# 2_waffling60-SE_matrix.net
KiCad netlist of a schematic drawn in Altium Designer
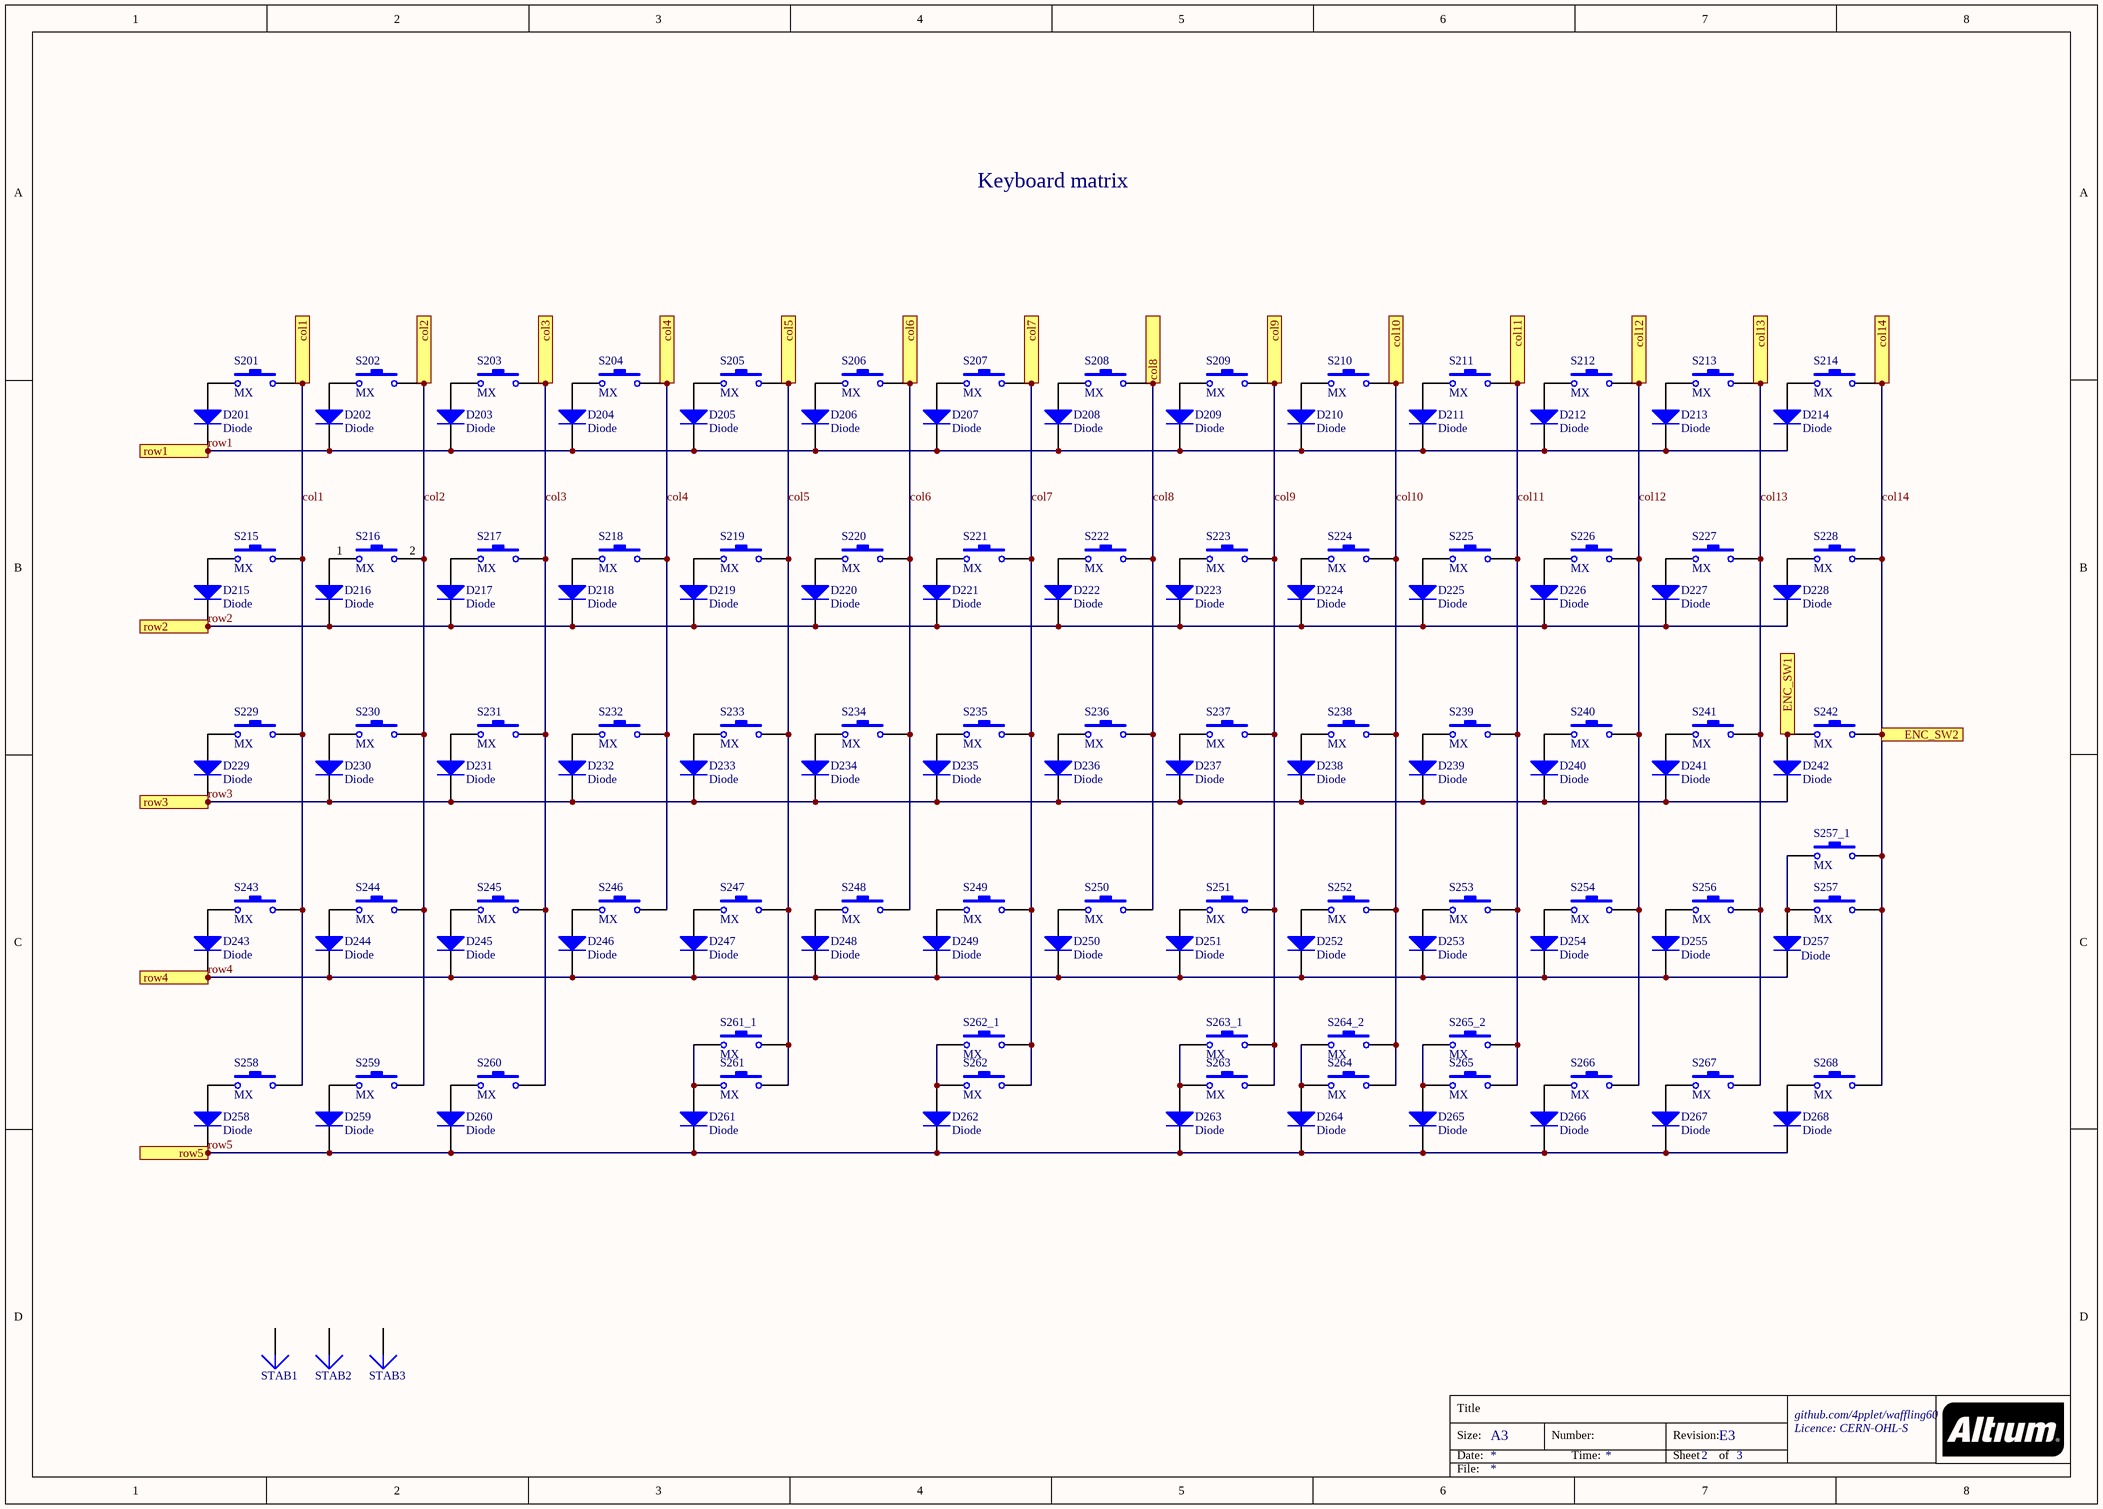
[diagram p0: 2_waffling60-SE_matrix.SchDoc]

(export (version "E")
  (design (tool "Eeschema 10.0.6"))
  (components
    (comp (ref "D201")
      (value "Diode")
      (footprint "SOD-123")
      (description "Default Diode")
      (fields (field (name "LCSC PART #") "C81598") (field (name "MRF.PART") "1N4148W"))
      (libsource (lib "Miscellaneous Devices") (part "Diode"))
    )
    (comp (ref "D202")
      (value "Diode")
      (footprint "SOD-123")
      (description "Default Diode")
      (fields (field (name "LCSC PART #") "C81598") (field (name "MRF.PART") "1N4148W"))
      (libsource (lib "Miscellaneous Devices") (part "Diode"))
    )
    (comp (ref "D203")
      (value "Diode")
      (footprint "SOD-123")
      (description "Default Diode")
      (fields (field (name "LCSC PART #") "C81598") (field (name "MRF.PART") "1N4148W"))
      (libsource (lib "Miscellaneous Devices") (part "Diode"))
    )
    (comp (ref "D204")
      (value "Diode")
      (footprint "SOD-123")
      (description "Default Diode")
      (fields (field (name "LCSC PART #") "C81598") (field (name "MRF.PART") "1N4148W"))
      (libsource (lib "Miscellaneous Devices") (part "Diode"))
    )
    (comp (ref "D205")
      (value "Diode")
      (footprint "SOD-123")
      (description "Default Diode")
      (fields (field (name "LCSC PART #") "C81598") (field (name "MRF.PART") "1N4148W"))
      (libsource (lib "Miscellaneous Devices") (part "Diode"))
    )
    (comp (ref "D206")
      (value "Diode")
      (footprint "SOD-123")
      (description "Default Diode")
      (fields (field (name "LCSC PART #") "C81598") (field (name "MRF.PART") "1N4148W"))
      (libsource (lib "Miscellaneous Devices") (part "Diode"))
    )
    (comp (ref "D207")
      (value "Diode")
      (footprint "SOD-123")
      (description "Default Diode")
      (fields (field (name "LCSC PART #") "C81598") (field (name "MRF.PART") "1N4148W"))
      (libsource (lib "Miscellaneous Devices") (part "Diode"))
    )
    (comp (ref "D208")
      (value "Diode")
      (footprint "SOD-123")
      (description "Default Diode")
      (fields (field (name "LCSC PART #") "C81598") (field (name "MRF.PART") "1N4148W"))
      (libsource (lib "Miscellaneous Devices") (part "Diode"))
    )
    (comp (ref "D209")
      (value "Diode")
      (footprint "SOD-123")
      (description "Default Diode")
      (fields (field (name "LCSC PART #") "C81598") (field (name "MRF.PART") "1N4148W"))
      (libsource (lib "Miscellaneous Devices") (part "Diode"))
    )
    (comp (ref "D210")
      (value "Diode")
      (footprint "SOD-123")
      (description "Default Diode")
      (fields (field (name "LCSC PART #") "C81598") (field (name "MRF.PART") "1N4148W"))
      (libsource (lib "Miscellaneous Devices") (part "Diode"))
    )
    (comp (ref "D211")
      (value "Diode")
      (footprint "SOD-123")
      (description "Default Diode")
      (fields (field (name "LCSC PART #") "C81598") (field (name "MRF.PART") "1N4148W"))
      (libsource (lib "Miscellaneous Devices") (part "Diode"))
    )
    (comp (ref "D212")
      (value "Diode")
      (footprint "SOD-123")
      (description "Default Diode")
      (fields (field (name "LCSC PART #") "C81598") (field (name "MRF.PART") "1N4148W"))
      (libsource (lib "Miscellaneous Devices") (part "Diode"))
    )
    (comp (ref "D213")
      (value "Diode")
      (footprint "SOD-123")
      (description "Default Diode")
      (fields (field (name "LCSC PART #") "C81598") (field (name "MRF.PART") "1N4148W"))
      (libsource (lib "Miscellaneous Devices") (part "Diode"))
    )
    (comp (ref "D214")
      (value "Diode")
      (footprint "SOD-123")
      (description "Default Diode")
      (fields (field (name "LCSC PART #") "C81598") (field (name "MRF.PART") "1N4148W"))
      (libsource (lib "Miscellaneous Devices") (part "Diode"))
    )
    (comp (ref "D215")
      (value "Diode")
      (footprint "SOD-123")
      (description "Default Diode")
      (fields (field (name "LCSC PART #") "C81598") (field (name "MRF.PART") "1N4148W"))
      (libsource (lib "Miscellaneous Devices") (part "Diode"))
    )
    (comp (ref "D216")
      (value "Diode")
      (footprint "SOD-123")
      (description "Default Diode")
      (fields (field (name "LCSC PART #") "C81598") (field (name "MRF.PART") "1N4148W"))
      (libsource (lib "Miscellaneous Devices") (part "Diode"))
    )
    (comp (ref "D217")
      (value "Diode")
      (footprint "SOD-123")
      (description "Default Diode")
      (fields (field (name "LCSC PART #") "C81598") (field (name "MRF.PART") "1N4148W"))
      (libsource (lib "Miscellaneous Devices") (part "Diode"))
    )
    (comp (ref "D218")
      (value "Diode")
      (footprint "SOD-123")
      (description "Default Diode")
      (fields (field (name "LCSC PART #") "C81598") (field (name "MRF.PART") "1N4148W"))
      (libsource (lib "Miscellaneous Devices") (part "Diode"))
    )
    (comp (ref "D219")
      (value "Diode")
      (footprint "SOD-123")
      (description "Default Diode")
      (fields (field (name "LCSC PART #") "C81598") (field (name "MRF.PART") "1N4148W"))
      (libsource (lib "Miscellaneous Devices") (part "Diode"))
    )
    (comp (ref "D220")
      (value "Diode")
      (footprint "SOD-123")
      (description "Default Diode")
      (fields (field (name "LCSC PART #") "C81598") (field (name "MRF.PART") "1N4148W"))
      (libsource (lib "Miscellaneous Devices") (part "Diode"))
    )
    (comp (ref "D221")
      (value "Diode")
      (footprint "SOD-123")
      (description "Default Diode")
      (fields (field (name "LCSC PART #") "C81598") (field (name "MRF.PART") "1N4148W"))
      (libsource (lib "Miscellaneous Devices") (part "Diode"))
    )
    (comp (ref "D222")
      (value "Diode")
      (footprint "SOD-123")
      (description "Default Diode")
      (fields (field (name "LCSC PART #") "C81598") (field (name "MRF.PART") "1N4148W"))
      (libsource (lib "Miscellaneous Devices") (part "Diode"))
    )
    (comp (ref "D223")
      (value "Diode")
      (footprint "SOD-123")
      (description "Default Diode")
      (fields (field (name "LCSC PART #") "C81598") (field (name "MRF.PART") "1N4148W"))
      (libsource (lib "Miscellaneous Devices") (part "Diode"))
    )
    (comp (ref "D224")
      (value "Diode")
      (footprint "SOD-123")
      (description "Default Diode")
      (fields (field (name "LCSC PART #") "C81598") (field (name "MRF.PART") "1N4148W"))
      (libsource (lib "Miscellaneous Devices") (part "Diode"))
    )
    (comp (ref "D225")
      (value "Diode")
      (footprint "SOD-123")
      (description "Default Diode")
      (fields (field (name "LCSC PART #") "C81598") (field (name "MRF.PART") "1N4148W"))
      (libsource (lib "Miscellaneous Devices") (part "Diode"))
    )
    (comp (ref "D226")
      (value "Diode")
      (footprint "SOD-123")
      (description "Default Diode")
      (fields (field (name "LCSC PART #") "C81598") (field (name "MRF.PART") "1N4148W"))
      (libsource (lib "Miscellaneous Devices") (part "Diode"))
    )
    (comp (ref "D227")
      (value "Diode")
      (footprint "SOD-123")
      (description "Default Diode")
      (fields (field (name "LCSC PART #") "C81598") (field (name "MRF.PART") "1N4148W"))
      (libsource (lib "Miscellaneous Devices") (part "Diode"))
    )
    (comp (ref "D228")
      (value "Diode")
      (footprint "SOD-123")
      (description "Default Diode")
      (fields (field (name "LCSC PART #") "C81598") (field (name "MRF.PART") "1N4148W"))
      (libsource (lib "Miscellaneous Devices") (part "Diode"))
    )
    (comp (ref "D229")
      (value "Diode")
      (footprint "SOD-123")
      (description "Default Diode")
      (fields (field (name "LCSC PART #") "C81598") (field (name "MRF.PART") "1N4148W"))
      (libsource (lib "Miscellaneous Devices") (part "Diode"))
    )
    (comp (ref "D230")
      (value "Diode")
      (footprint "SOD-123")
      (description "Default Diode")
      (fields (field (name "LCSC PART #") "C81598") (field (name "MRF.PART") "1N4148W"))
      (libsource (lib "Miscellaneous Devices") (part "Diode"))
    )
    (comp (ref "D231")
      (value "Diode")
      (footprint "SOD-123")
      (description "Default Diode")
      (fields (field (name "LCSC PART #") "C81598") (field (name "MRF.PART") "1N4148W"))
      (libsource (lib "Miscellaneous Devices") (part "Diode"))
    )
    (comp (ref "D232")
      (value "Diode")
      (footprint "SOD-123")
      (description "Default Diode")
      (fields (field (name "LCSC PART #") "C81598") (field (name "MRF.PART") "1N4148W"))
      (libsource (lib "Miscellaneous Devices") (part "Diode"))
    )
    (comp (ref "D233")
      (value "Diode")
      (footprint "SOD-123")
      (description "Default Diode")
      (fields (field (name "LCSC PART #") "C81598") (field (name "MRF.PART") "1N4148W"))
      (libsource (lib "Miscellaneous Devices") (part "Diode"))
    )
    (comp (ref "D234")
      (value "Diode")
      (footprint "SOD-123")
      (description "Default Diode")
      (fields (field (name "LCSC PART #") "C81598") (field (name "MRF.PART") "1N4148W"))
      (libsource (lib "Miscellaneous Devices") (part "Diode"))
    )
    (comp (ref "D235")
      (value "Diode")
      (footprint "SOD-123")
      (description "Default Diode")
      (fields (field (name "LCSC PART #") "C81598") (field (name "MRF.PART") "1N4148W"))
      (libsource (lib "Miscellaneous Devices") (part "Diode"))
    )
    (comp (ref "D236")
      (value "Diode")
      (footprint "SOD-123")
      (description "Default Diode")
      (fields (field (name "LCSC PART #") "C81598") (field (name "MRF.PART") "1N4148W"))
      (libsource (lib "Miscellaneous Devices") (part "Diode"))
    )
    (comp (ref "D237")
      (value "Diode")
      (footprint "SOD-123")
      (description "Default Diode")
      (fields (field (name "LCSC PART #") "C81598") (field (name "MRF.PART") "1N4148W"))
      (libsource (lib "Miscellaneous Devices") (part "Diode"))
    )
    (comp (ref "D238")
      (value "Diode")
      (footprint "SOD-123")
      (description "Default Diode")
      (fields (field (name "LCSC PART #") "C81598") (field (name "MRF.PART") "1N4148W"))
      (libsource (lib "Miscellaneous Devices") (part "Diode"))
    )
    (comp (ref "D239")
      (value "Diode")
      (footprint "SOD-123")
      (description "Default Diode")
      (fields (field (name "LCSC PART #") "C81598") (field (name "MRF.PART") "1N4148W"))
      (libsource (lib "Miscellaneous Devices") (part "Diode"))
    )
    (comp (ref "D240")
      (value "Diode")
      (footprint "SOD-123")
      (description "Default Diode")
      (fields (field (name "LCSC PART #") "C81598") (field (name "MRF.PART") "1N4148W"))
      (libsource (lib "Miscellaneous Devices") (part "Diode"))
    )
    (comp (ref "D241")
      (value "Diode")
      (footprint "SOD-123")
      (description "Default Diode")
      (fields (field (name "LCSC PART #") "C81598") (field (name "MRF.PART") "1N4148W"))
      (libsource (lib "Miscellaneous Devices") (part "Diode"))
    )
    (comp (ref "D242")
      (value "Diode")
      (footprint "SOD-123")
      (description "Default Diode")
      (fields (field (name "LCSC PART #") "C81598") (field (name "MRF.PART") "1N4148W"))
      (libsource (lib "Miscellaneous Devices") (part "Diode"))
    )
    (comp (ref "D243")
      (value "Diode")
      (footprint "SOD-123")
      (description "Default Diode")
      (fields (field (name "LCSC PART #") "C81598") (field (name "MRF.PART") "1N4148W"))
      (libsource (lib "Miscellaneous Devices") (part "Diode"))
    )
    (comp (ref "D244")
      (value "Diode")
      (footprint "SOD-123")
      (description "Default Diode")
      (fields (field (name "LCSC PART #") "C81598") (field (name "MRF.PART") "1N4148W"))
      (libsource (lib "Miscellaneous Devices") (part "Diode"))
    )
    (comp (ref "D245")
      (value "Diode")
      (footprint "SOD-123")
      (description "Default Diode")
      (fields (field (name "LCSC PART #") "C81598") (field (name "MRF.PART") "1N4148W"))
      (libsource (lib "Miscellaneous Devices") (part "Diode"))
    )
    (comp (ref "D246")
      (value "Diode")
      (footprint "SOD-123")
      (description "Default Diode")
      (fields (field (name "LCSC PART #") "C81598") (field (name "MRF.PART") "1N4148W"))
      (libsource (lib "Miscellaneous Devices") (part "Diode"))
    )
    (comp (ref "D247")
      (value "Diode")
      (footprint "SOD-123")
      (description "Default Diode")
      (fields (field (name "LCSC PART #") "C81598") (field (name "MRF.PART") "1N4148W"))
      (libsource (lib "Miscellaneous Devices") (part "Diode"))
    )
    (comp (ref "D248")
      (value "Diode")
      (footprint "SOD-123")
      (description "Default Diode")
      (fields (field (name "LCSC PART #") "C81598") (field (name "MRF.PART") "1N4148W"))
      (libsource (lib "Miscellaneous Devices") (part "Diode"))
    )
    (comp (ref "D249")
      (value "Diode")
      (footprint "SOD-123")
      (description "Default Diode")
      (fields (field (name "LCSC PART #") "C81598") (field (name "MRF.PART") "1N4148W"))
      (libsource (lib "Miscellaneous Devices") (part "Diode"))
    )
    (comp (ref "D250")
      (value "Diode")
      (footprint "SOD-123")
      (description "Default Diode")
      (fields (field (name "LCSC PART #") "C81598") (field (name "MRF.PART") "1N4148W"))
      (libsource (lib "Miscellaneous Devices") (part "Diode"))
    )
    (comp (ref "D251")
      (value "Diode")
      (footprint "SOD-123")
      (description "Default Diode")
      (fields (field (name "LCSC PART #") "C81598") (field (name "MRF.PART") "1N4148W"))
      (libsource (lib "Miscellaneous Devices") (part "Diode"))
    )
    (comp (ref "D252")
      (value "Diode")
      (footprint "SOD-123")
      (description "Default Diode")
      (fields (field (name "LCSC PART #") "C81598") (field (name "MRF.PART") "1N4148W"))
      (libsource (lib "Miscellaneous Devices") (part "Diode"))
    )
    (comp (ref "D253")
      (value "Diode")
      (footprint "SOD-123")
      (description "Default Diode")
      (fields (field (name "LCSC PART #") "C81598") (field (name "MRF.PART") "1N4148W"))
      (libsource (lib "Miscellaneous Devices") (part "Diode"))
    )
    (comp (ref "D254")
      (value "Diode")
      (footprint "SOD-123")
      (description "Default Diode")
      (fields (field (name "LCSC PART #") "C81598") (field (name "MRF.PART") "1N4148W"))
      (libsource (lib "Miscellaneous Devices") (part "Diode"))
    )
    (comp (ref "D255")
      (value "Diode")
      (footprint "SOD-123")
      (description "Default Diode")
      (fields (field (name "LCSC PART #") "C81598") (field (name "MRF.PART") "1N4148W"))
      (libsource (lib "Miscellaneous Devices") (part "Diode"))
    )
    (comp (ref "D257")
      (value "Diode")
      (footprint "SOD-123")
      (description "Default Diode")
      (fields (field (name "LCSC PART #") "C81598") (field (name "MRF.PART") "1N4148W"))
      (libsource (lib "Miscellaneous Devices") (part "Diode"))
    )
    (comp (ref "D258")
      (value "Diode")
      (footprint "SOD-123")
      (description "Default Diode")
      (fields (field (name "LCSC PART #") "C81598") (field (name "MRF.PART") "1N4148W"))
      (libsource (lib "Miscellaneous Devices") (part "Diode"))
    )
    (comp (ref "D259")
      (value "Diode")
      (footprint "SOD-123")
      (description "Default Diode")
      (fields (field (name "LCSC PART #") "C81598") (field (name "MRF.PART") "1N4148W"))
      (libsource (lib "Miscellaneous Devices") (part "Diode"))
    )
    (comp (ref "D260")
      (value "Diode")
      (footprint "SOD-123")
      (description "Default Diode")
      (fields (field (name "LCSC PART #") "C81598") (field (name "MRF.PART") "1N4148W"))
      (libsource (lib "Miscellaneous Devices") (part "Diode"))
    )
    (comp (ref "D261")
      (value "Diode")
      (footprint "SOD-123")
      (description "Default Diode")
      (fields (field (name "LCSC PART #") "C81598") (field (name "MRF.PART") "1N4148W"))
      (libsource (lib "Miscellaneous Devices") (part "Diode"))
    )
    (comp (ref "D262")
      (value "Diode")
      (footprint "SOD-123")
      (description "Default Diode")
      (fields (field (name "LCSC PART #") "C81598") (field (name "MRF.PART") "1N4148W"))
      (libsource (lib "Miscellaneous Devices") (part "Diode"))
    )
    (comp (ref "D263")
      (value "Diode")
      (footprint "SOD-123")
      (description "Default Diode")
      (fields (field (name "LCSC PART #") "C81598") (field (name "MRF.PART") "1N4148W"))
      (libsource (lib "Miscellaneous Devices") (part "Diode"))
    )
    (comp (ref "D264")
      (value "Diode")
      (footprint "SOD-123")
      (description "Default Diode")
      (fields (field (name "LCSC PART #") "C81598") (field (name "MRF.PART") "1N4148W"))
      (libsource (lib "Miscellaneous Devices") (part "Diode"))
    )
    (comp (ref "D265")
      (value "Diode")
      (footprint "SOD-123")
      (description "Default Diode")
      (fields (field (name "LCSC PART #") "C81598") (field (name "MRF.PART") "1N4148W"))
      (libsource (lib "Miscellaneous Devices") (part "Diode"))
    )
    (comp (ref "D266")
      (value "Diode")
      (footprint "SOD-123")
      (description "Default Diode")
      (fields (field (name "LCSC PART #") "C81598") (field (name "MRF.PART") "1N4148W"))
      (libsource (lib "Miscellaneous Devices") (part "Diode"))
    )
    (comp (ref "D267")
      (value "Diode")
      (footprint "SOD-123")
      (description "Default Diode")
      (fields (field (name "LCSC PART #") "C81598") (field (name "MRF.PART") "1N4148W"))
      (libsource (lib "Miscellaneous Devices") (part "Diode"))
    )
    (comp (ref "D268")
      (value "Diode")
      (footprint "SOD-123")
      (description "Default Diode")
      (fields (field (name "LCSC PART #") "C81598") (field (name "MRF.PART") "1N4148W"))
      (libsource (lib "Miscellaneous Devices") (part "Diode"))
    )
    (comp (ref "S201")
      (value "MX")
      (footprint "MX-switch - switched pol")
      (description "Switch")
      (libsource (lib "Miscellaneous Devices") (part "SW-PB"))
    )
    (comp (ref "S202")
      (value "MX")
      (footprint "MX-switch")
      (description "Switch")
      (libsource (lib "Miscellaneous Devices") (part "SW-PB"))
    )
    (comp (ref "S203")
      (value "MX")
      (footprint "MX-switch - switched pol")
      (description "Switch")
      (libsource (lib "Miscellaneous Devices") (part "SW-PB"))
    )
    (comp (ref "S204")
      (value "MX")
      (footprint "MX-switch - switched pol")
      (description "Switch")
      (libsource (lib "Miscellaneous Devices") (part "SW-PB"))
    )
    (comp (ref "S205")
      (value "MX")
      (footprint "MX-switch - switched pol")
      (description "Switch")
      (libsource (lib "Miscellaneous Devices") (part "SW-PB"))
    )
    (comp (ref "S206")
      (value "MX")
      (footprint "MX-switch - switched pol")
      (description "Switch")
      (libsource (lib "Miscellaneous Devices") (part "SW-PB"))
    )
    (comp (ref "S207")
      (value "MX")
      (footprint "MX-switch - switched pol")
      (description "Switch")
      (libsource (lib "Miscellaneous Devices") (part "SW-PB"))
    )
    (comp (ref "S208")
      (value "MX")
      (footprint "MX-switch - switched pol")
      (description "Switch")
      (libsource (lib "Miscellaneous Devices") (part "SW-PB"))
    )
    (comp (ref "S209")
      (value "MX")
      (footprint "MX-switch - switched pol")
      (description "Switch")
      (libsource (lib "Miscellaneous Devices") (part "SW-PB"))
    )
    (comp (ref "S210")
      (value "MX")
      (footprint "MX-switch - switched pol")
      (description "Switch")
      (libsource (lib "Miscellaneous Devices") (part "SW-PB"))
    )
    (comp (ref "S211")
      (value "MX")
      (footprint "MX-switch - switched pol")
      (description "Switch")
      (libsource (lib "Miscellaneous Devices") (part "SW-PB"))
    )
    (comp (ref "S212")
      (value "MX")
      (footprint "MX-switch - switched pol")
      (description "Switch")
      (libsource (lib "Miscellaneous Devices") (part "SW-PB"))
    )
    (comp (ref "S213")
      (value "MX")
      (footprint "MX-switch - switched pol")
      (description "Switch")
      (libsource (lib "Miscellaneous Devices") (part "SW-PB"))
    )
    (comp (ref "S214")
      (value "MX")
      (footprint "MX-switch")
      (description "Switch")
      (libsource (lib "Miscellaneous Devices") (part "SW-PB"))
    )
    (comp (ref "S215")
      (value "MX")
      (footprint "MX-switch - switched pol")
      (description "TAB")
      (libsource (lib "Miscellaneous Devices") (part "SW-PB"))
    )
    (comp (ref "S216")
      (value "MX")
      (footprint "MX-switch")
      (description "Switch")
      (libsource (lib "") (part "SW-PB_1"))
    )
    (comp (ref "S217")
      (value "MX")
      (footprint "MX-switch - switched pol")
      (description "Switch")
      (libsource (lib "Miscellaneous Devices") (part "SW-PB"))
    )
    (comp (ref "S218")
      (value "MX")
      (footprint "MX-switch - switched pol")
      (description "Switch")
      (libsource (lib "Miscellaneous Devices") (part "SW-PB"))
    )
    (comp (ref "S219")
      (value "MX")
      (footprint "MX-switch - switched pol")
      (description "Switch")
      (libsource (lib "Miscellaneous Devices") (part "SW-PB"))
    )
    (comp (ref "S220")
      (value "MX")
      (footprint "MX-switch - switched pol")
      (description "Switch")
      (libsource (lib "Miscellaneous Devices") (part "SW-PB"))
    )
    (comp (ref "S221")
      (value "MX")
      (footprint "MX-switch - switched pol")
      (description "Switch")
      (libsource (lib "Miscellaneous Devices") (part "SW-PB"))
    )
    (comp (ref "S222")
      (value "MX")
      (footprint "MX-switch - switched pol")
      (description "Switch")
      (libsource (lib "Miscellaneous Devices") (part "SW-PB"))
    )
    (comp (ref "S223")
      (value "MX")
      (footprint "MX-switch - switched pol")
      (description "Switch")
      (libsource (lib "Miscellaneous Devices") (part "SW-PB"))
    )
    (comp (ref "S224")
      (value "MX")
      (footprint "MX-switch - switched pol")
      (description "Switch")
      (libsource (lib "Miscellaneous Devices") (part "SW-PB"))
    )
    (comp (ref "S225")
      (value "MX")
      (footprint "MX-switch - switched pol")
      (description "Switch")
      (libsource (lib "Miscellaneous Devices") (part "SW-PB"))
    )
    (comp (ref "S226")
      (value "MX")
      (footprint "MX-switch")
      (description "Switch")
      (libsource (lib "Miscellaneous Devices") (part "SW-PB"))
    )
    (comp (ref "S227")
      (value "MX")
      (footprint "MX-switch")
      (description "Switch")
      (libsource (lib "Miscellaneous Devices") (part "SW-PB"))
    )
    (comp (ref "S228")
      (value "MX")
      (footprint "MX-switch - 1.5U")
      (description "Switch")
      (libsource (lib "Miscellaneous Devices") (part "SW-PB"))
    )
    (comp (ref "S229")
      (value "MX")
      (footprint "MX-switch - CAPS")
      (description "Switch")
      (libsource (lib "Miscellaneous Devices") (part "SW-PB"))
    )
    (comp (ref "S230")
      (value "MX")
      (footprint "MX-switch")
      (description "Switch")
      (libsource (lib "Miscellaneous Devices") (part "SW-PB"))
    )
    (comp (ref "S231")
      (value "MX")
      (footprint "MX-switch - switched pol")
      (description "Switch")
      (libsource (lib "Miscellaneous Devices") (part "SW-PB"))
    )
    (comp (ref "S232")
      (value "MX")
      (footprint "MX-switch - switched pol")
      (description "Switch")
      (libsource (lib "Miscellaneous Devices") (part "SW-PB"))
    )
    (comp (ref "S233")
      (value "MX")
      (footprint "MX-switch - switched pol")
      (description "Switch")
      (libsource (lib "Miscellaneous Devices") (part "SW-PB"))
    )
    (comp (ref "S234")
      (value "MX")
      (footprint "MX-switch - switched pol")
      (description "Switch")
      (libsource (lib "Miscellaneous Devices") (part "SW-PB"))
    )
    (comp (ref "S235")
      (value "MX")
      (footprint "MX-switch - switched pol")
      (description "Switch")
      (libsource (lib "Miscellaneous Devices") (part "SW-PB"))
    )
    (comp (ref "S236")
      (value "MX")
      (footprint "MX-switch - switched pol")
      (description "Switch")
      (libsource (lib "Miscellaneous Devices") (part "SW-PB"))
    )
    (comp (ref "S237")
      (value "MX")
      (footprint "MX-switch - switched pol")
      (description "Switch")
      (libsource (lib "Miscellaneous Devices") (part "SW-PB"))
    )
    (comp (ref "S238")
      (value "MX")
      (footprint "MX-switch - switched pol")
      (description "Switch")
      (libsource (lib "Miscellaneous Devices") (part "SW-PB"))
    )
    (comp (ref "S239")
      (value "MX")
      (footprint "MX-switch - switched pol")
      (description "Switch")
      (libsource (lib "Miscellaneous Devices") (part "SW-PB"))
    )
    (comp (ref "S240")
      (value "MX")
      (footprint "MX-switch - switched pol")
      (description "Switch")
      (libsource (lib "Miscellaneous Devices") (part "SW-PB"))
    )
    (comp (ref "S241")
      (value "MX")
      (footprint "MX-switch")
      (description "Switch")
      (libsource (lib "Miscellaneous Devices") (part "SW-PB"))
    )
    (comp (ref "S242")
      (value "MX")
      (footprint "MX-switch - backspace")
      (description "Switch")
      (libsource (lib "Miscellaneous Devices") (part "SW-PB"))
    )
    (comp (ref "S243")
      (value "MX")
      (footprint "MX-switch - Left shift")
      (description "Switch")
      (libsource (lib "Miscellaneous Devices") (part "SW-PB"))
    )
    (comp (ref "S244")
      (value "MX")
      (footprint "MX-switch")
      (description "Switch")
      (libsource (lib "Miscellaneous Devices") (part "SW-PB"))
    )
    (comp (ref "S245")
      (value "MX")
      (footprint "MX-switch - switched pol")
      (description "Switch")
      (libsource (lib "Miscellaneous Devices") (part "SW-PB"))
    )
    (comp (ref "S246")
      (value "MX")
      (footprint "MX-switch - switched pol")
      (description "Switch")
      (libsource (lib "Miscellaneous Devices") (part "SW-PB"))
    )
    (comp (ref "S247")
      (value "MX")
      (footprint "MX-switch - switched pol")
      (description "Switch")
      (libsource (lib "Miscellaneous Devices") (part "SW-PB"))
    )
    (comp (ref "S248")
      (value "MX")
      (footprint "MX-switch - switched pol")
      (description "Switch")
      (libsource (lib "Miscellaneous Devices") (part "SW-PB"))
    )
    (comp (ref "S249")
      (value "MX")
      (footprint "MX-switch - switched pol")
      (description "Switch")
      (libsource (lib "Miscellaneous Devices") (part "SW-PB"))
    )
    (comp (ref "S250")
      (value "MX")
      (footprint "MX-switch - switched pol")
      (description "Switch")
      (libsource (lib "Miscellaneous Devices") (part "SW-PB"))
    )
    (comp (ref "S251")
      (value "MX")
      (footprint "MX-switch - switched pol")
      (description "Switch")
      (libsource (lib "Miscellaneous Devices") (part "SW-PB"))
    )
    (comp (ref "S252")
      (value "MX")
      (footprint "MX-switch - switched pol")
      (description "Switch")
      (libsource (lib "Miscellaneous Devices") (part "SW-PB"))
    )
    (comp (ref "S253")
      (value "MX")
      (footprint "MX-switch - switched pol")
      (description "Switch")
      (libsource (lib "Miscellaneous Devices") (part "SW-PB"))
    )
    (comp (ref "S254")
      (value "MX")
      (footprint "MX-switch - switched pol")
      (description "Switch")
      (libsource (lib "Miscellaneous Devices") (part "SW-PB"))
    )
    (comp (ref "S256")
      (value "MX")
      (footprint "MX-switch - right shift")
      (description "Switch")
      (libsource (lib "Miscellaneous Devices") (part "SW-PB"))
    )
    (comp (ref "S257")
      (value "MX")
      (footprint "MX-switch")
      (description "Switch")
      (libsource (lib "Miscellaneous Devices") (part "SW-PB"))
    )
    (comp (ref "S257_1")
      (value "MX")
      (footprint "MX-switch")
      (description "Switch")
      (libsource (lib "Miscellaneous Devices") (part "SW-PB"))
    )
    (comp (ref "S258")
      (value "MX")
      (footprint "MX-switch - 1.5u MOD-L")
      (description "Switch")
      (libsource (lib "Miscellaneous Devices") (part "SW-PB"))
    )
    (comp (ref "S259")
      (value "MX")
      (footprint "MX-switch - 1u MOD-L")
      (description "Switch")
      (libsource (lib "Miscellaneous Devices") (part "SW-PB"))
    )
    (comp (ref "S260")
      (value "MX")
      (footprint "MX-switch - 1.5u MOD-L")
      (description "Switch")
      (libsource (lib "Miscellaneous Devices") (part "SW-PB"))
    )
    (comp (ref "S261")
      (value "MX")
      (footprint "MX-SWITCH - L SPLIT SPACE_V2")
      (description "Switch")
      (libsource (lib "Miscellaneous Devices") (part "SW-PB"))
    )
    (comp (ref "S261_1")
      (value "MX")
      (footprint "MX-switch - 3U - rotated stab")
      (description "Switch")
      (libsource (lib "Miscellaneous Devices") (part "SW-PB"))
    )
    (comp (ref "S262")
      (value "MX")
      (footprint "MX-SWITCH - SPACE_7U+6.27U+6U")
      (description "Switch")
      (libsource (lib "Miscellaneous Devices") (part "SW-PB"))
    )
    (comp (ref "S262_1")
      (value "MX")
      (footprint "MX-switch - switched pol")
      (description "Switch")
      (libsource (lib "Miscellaneous Devices") (part "SW-PB"))
    )
    (comp (ref "S263")
      (value "MX")
      (footprint "MX-SWITCH - R SPLIT SPACE_V2")
      (description "Switch")
      (libsource (lib "Miscellaneous Devices") (part "SW-PB"))
    )
    (comp (ref "S263_1")
      (value "MX")
      (footprint "MX-switch - 3U - rotated stab")
      (description "Switch")
      (libsource (lib "Miscellaneous Devices") (part "SW-PB"))
    )
    (comp (ref "S264")
      (value "MX")
      (footprint "MX-switch - switched pol")
      (description "Switch")
      (libsource (lib "Miscellaneous Devices") (part "SW-PB"))
    )
    (comp (ref "S264_2")
      (value "MX")
      (footprint "MX-switch - switched pol")
      (description "Switch")
      (libsource (lib "Miscellaneous Devices") (part "SW-PB"))
    )
    (comp (ref "S265")
      (value "MX")
      (footprint "MX-switch - 1.5u MOD-R")
      (description "Switch")
      (libsource (lib "Miscellaneous Devices") (part "SW-PB"))
    )
    (comp (ref "S265_2")
      (value "MX")
      (footprint "MX-switch - switched pol")
      (description "Switch")
      (libsource (lib "Miscellaneous Devices") (part "SW-PB"))
    )
    (comp (ref "S266")
      (value "MX")
      (footprint "MX-switch - 1u MOD-R")
      (description "Switch")
      (libsource (lib "Miscellaneous Devices") (part "SW-PB"))
    )
    (comp (ref "S267")
      (value "MX")
      (footprint "MX-switch - 1.5u MOD-R")
      (description "Switch")
      (libsource (lib "Miscellaneous Devices") (part "SW-PB"))
    )
    (comp (ref "S268")
      (value "MX")
      (footprint "MX-switch")
      (description "Switch")
      (libsource (lib "Miscellaneous Devices") (part "SW-PB"))
    )
    (comp (ref "STAB1")
      (value "Plug")
      (footprint "Stab 10U")
      (libsource (lib "Miscellaneous Connectors") (part "Plug"))
    )
    (comp (ref "STAB2")
      (value "Plug")
      (footprint "Stab 2u")
      (libsource (lib "Miscellaneous Connectors") (part "Plug"))
    )
    (comp (ref "STAB3")
      (value "Plug")
      (footprint "Stab 2u")
      (libsource (lib "Miscellaneous Connectors") (part "Plug"))
    )
  )
  (nets
    (net (code "1") (name "/ENC_SW1") (class "Default")
      (node (ref "D242") (pin "1") (pinfunction "A_1") (pintype "passive"))
      (node (ref "S242") (pin "1") (pinfunction "1_1") (pintype "passive"))
    )
    (net (code "2") (name "/col1") (class "Default")
      (node (ref "S201") (pin "2") (pinfunction "2_2") (pintype "passive"))
      (node (ref "S215") (pin "2") (pinfunction "2_2") (pintype "passive"))
      (node (ref "S229") (pin "1") (pinfunction "1_1") (pintype "passive"))
      (node (ref "S243") (pin "2") (pinfunction "2_2") (pintype "passive"))
      (node (ref "S258") (pin "1") (pinfunction "1_1") (pintype "passive"))
    )
    (net (code "3") (name "/col2") (class "Default")
      (node (ref "S202") (pin "2") (pinfunction "2_2") (pintype "passive"))
      (node (ref "S216") (pin "2") (pinfunction "2_2") (pintype "passive"))
      (node (ref "S230") (pin "2") (pinfunction "2_2") (pintype "passive"))
      (node (ref "S244") (pin "1") (pinfunction "1_1") (pintype "passive"))
      (node (ref "S259") (pin "2") (pinfunction "2_2") (pintype "passive"))
    )
    (net (code "4") (name "/col3") (class "Default")
      (node (ref "S203") (pin "2") (pinfunction "2_2") (pintype "passive"))
      (node (ref "S217") (pin "2") (pinfunction "2_2") (pintype "passive"))
      (node (ref "S231") (pin "2") (pinfunction "2_2") (pintype "passive"))
      (node (ref "S245") (pin "2") (pinfunction "2_2") (pintype "passive"))
      (node (ref "S260") (pin "2") (pinfunction "2_2") (pintype "passive"))
    )
    (net (code "5") (name "/col4") (class "Default")
      (node (ref "S204") (pin "2") (pinfunction "2_2") (pintype "passive"))
      (node (ref "S218") (pin "2") (pinfunction "2_2") (pintype "passive"))
      (node (ref "S232") (pin "2") (pinfunction "2_2") (pintype "passive"))
      (node (ref "S246") (pin "2") (pinfunction "2_2") (pintype "passive"))
    )
    (net (code "6") (name "/col5") (class "Default")
      (node (ref "S205") (pin "2") (pinfunction "2_2") (pintype "passive"))
      (node (ref "S219") (pin "2") (pinfunction "2_2") (pintype "passive"))
      (node (ref "S233") (pin "2") (pinfunction "2_2") (pintype "passive"))
      (node (ref "S247") (pin "2") (pinfunction "2_2") (pintype "passive"))
      (node (ref "S261") (pin "2") (pinfunction "2_2") (pintype "passive"))
      (node (ref "S261_1") (pin "2") (pinfunction "2_2") (pintype "passive"))
    )
    (net (code "7") (name "/col6") (class "Default")
      (node (ref "S206") (pin "2") (pinfunction "2_2") (pintype "passive"))
      (node (ref "S220") (pin "2") (pinfunction "2_2") (pintype "passive"))
      (node (ref "S234") (pin "2") (pinfunction "2_2") (pintype "passive"))
      (node (ref "S248") (pin "2") (pinfunction "2_2") (pintype "passive"))
    )
    (net (code "8") (name "/col7") (class "Default")
      (node (ref "S207") (pin "2") (pinfunction "2_2") (pintype "passive"))
      (node (ref "S221") (pin "2") (pinfunction "2_2") (pintype "passive"))
      (node (ref "S235") (pin "2") (pinfunction "2_2") (pintype "passive"))
      (node (ref "S249") (pin "2") (pinfunction "2_2") (pintype "passive"))
      (node (ref "S262") (pin "1") (pinfunction "1_1") (pintype "passive"))
      (node (ref "S262_1") (pin "2") (pinfunction "2_2") (pintype "passive"))
    )
    (net (code "9") (name "/col8") (class "Default")
      (node (ref "S208") (pin "2") (pinfunction "2_2") (pintype "passive"))
      (node (ref "S222") (pin "2") (pinfunction "2_2") (pintype "passive"))
      (node (ref "S236") (pin "2") (pinfunction "2_2") (pintype "passive"))
      (node (ref "S250") (pin "2") (pinfunction "2_2") (pintype "passive"))
    )
    (net (code "10") (name "/col9") (class "Default")
      (node (ref "S209") (pin "2") (pinfunction "2_2") (pintype "passive"))
      (node (ref "S223") (pin "2") (pinfunction "2_2") (pintype "passive"))
      (node (ref "S237") (pin "2") (pinfunction "2_2") (pintype "passive"))
      (node (ref "S251") (pin "2") (pinfunction "2_2") (pintype "passive"))
      (node (ref "S263") (pin "1") (pinfunction "1_1") (pintype "passive"))
      (node (ref "S263_1") (pin "1") (pinfunction "1_1") (pintype "passive"))
    )
    (net (code "11") (name "/col10") (class "Default")
      (node (ref "S210") (pin "2") (pinfunction "2_2") (pintype "passive"))
      (node (ref "S224") (pin "2") (pinfunction "2_2") (pintype "passive"))
      (node (ref "S238") (pin "2") (pinfunction "2_2") (pintype "passive"))
      (node (ref "S252") (pin "2") (pinfunction "2_2") (pintype "passive"))
      (node (ref "S264") (pin "2") (pinfunction "2_2") (pintype "passive"))
      (node (ref "S264_2") (pin "2") (pinfunction "2_2") (pintype "passive"))
    )
    (net (code "12") (name "/col11") (class "Default")
      (node (ref "S211") (pin "2") (pinfunction "2_2") (pintype "passive"))
      (node (ref "S225") (pin "2") (pinfunction "2_2") (pintype "passive"))
      (node (ref "S239") (pin "2") (pinfunction "2_2") (pintype "passive"))
      (node (ref "S253") (pin "2") (pinfunction "2_2") (pintype "passive"))
      (node (ref "S265") (pin "1") (pinfunction "1_1") (pintype "passive"))
      (node (ref "S265_2") (pin "2") (pinfunction "2_2") (pintype "passive"))
    )
    (net (code "13") (name "/col12") (class "Default")
      (node (ref "S212") (pin "2") (pinfunction "2_2") (pintype "passive"))
      (node (ref "S226") (pin "2") (pinfunction "2_2") (pintype "passive"))
      (node (ref "S240") (pin "2") (pinfunction "2_2") (pintype "passive"))
      (node (ref "S254") (pin "2") (pinfunction "2_2") (pintype "passive"))
      (node (ref "S266") (pin "1") (pinfunction "1_1") (pintype "passive"))
    )
    (net (code "14") (name "/col13") (class "Default")
      (node (ref "S213") (pin "2") (pinfunction "2_2") (pintype "passive"))
      (node (ref "S227") (pin "2") (pinfunction "2_2") (pintype "passive"))
      (node (ref "S241") (pin "2") (pinfunction "2_2") (pintype "passive"))
      (node (ref "S256") (pin "2") (pinfunction "2_2") (pintype "passive"))
      (node (ref "S267") (pin "2") (pinfunction "2_2") (pintype "passive"))
    )
    (net (code "15") (name "/col14") (class "Default")
      (node (ref "S214") (pin "2") (pinfunction "2_2") (pintype "passive"))
      (node (ref "S228") (pin "2") (pinfunction "2_2") (pintype "passive"))
      (node (ref "S242") (pin "2") (pinfunction "2_2") (pintype "passive"))
      (node (ref "S257") (pin "2") (pinfunction "2_2") (pintype "passive"))
      (node (ref "S257_1") (pin "2") (pinfunction "2_2") (pintype "passive"))
      (node (ref "S268") (pin "2") (pinfunction "2_2") (pintype "passive"))
    )
    (net (code "16") (name "/row1") (class "Default")
      (node (ref "D201") (pin "2") (pinfunction "K_2") (pintype "passive"))
      (node (ref "D202") (pin "2") (pinfunction "K_2") (pintype "passive"))
      (node (ref "D203") (pin "2") (pinfunction "K_2") (pintype "passive"))
      (node (ref "D204") (pin "2") (pinfunction "K_2") (pintype "passive"))
      (node (ref "D205") (pin "2") (pinfunction "K_2") (pintype "passive"))
      (node (ref "D206") (pin "2") (pinfunction "K_2") (pintype "passive"))
      (node (ref "D207") (pin "2") (pinfunction "K_2") (pintype "passive"))
      (node (ref "D208") (pin "2") (pinfunction "K_2") (pintype "passive"))
      (node (ref "D209") (pin "2") (pinfunction "K_2") (pintype "passive"))
      (node (ref "D210") (pin "2") (pinfunction "K_2") (pintype "passive"))
      (node (ref "D211") (pin "2") (pinfunction "K_2") (pintype "passive"))
      (node (ref "D212") (pin "2") (pinfunction "K_2") (pintype "passive"))
      (node (ref "D213") (pin "2") (pinfunction "K_2") (pintype "passive"))
      (node (ref "D214") (pin "2") (pinfunction "K_2") (pintype "passive"))
    )
    (net (code "17") (name "/row2") (class "Default")
      (node (ref "D215") (pin "2") (pinfunction "K_2") (pintype "passive"))
      (node (ref "D216") (pin "2") (pinfunction "K_2") (pintype "passive"))
      (node (ref "D217") (pin "2") (pinfunction "K_2") (pintype "passive"))
      (node (ref "D218") (pin "2") (pinfunction "K_2") (pintype "passive"))
      (node (ref "D219") (pin "2") (pinfunction "K_2") (pintype "passive"))
      (node (ref "D220") (pin "2") (pinfunction "K_2") (pintype "passive"))
      (node (ref "D221") (pin "2") (pinfunction "K_2") (pintype "passive"))
      (node (ref "D222") (pin "2") (pinfunction "K_2") (pintype "passive"))
      (node (ref "D223") (pin "2") (pinfunction "K_2") (pintype "passive"))
      (node (ref "D224") (pin "2") (pinfunction "K_2") (pintype "passive"))
      (node (ref "D225") (pin "2") (pinfunction "K_2") (pintype "passive"))
      (node (ref "D226") (pin "2") (pinfunction "K_2") (pintype "passive"))
      (node (ref "D227") (pin "2") (pinfunction "K_2") (pintype "passive"))
      (node (ref "D228") (pin "2") (pinfunction "K_2") (pintype "passive"))
    )
    (net (code "18") (name "/row3") (class "Default")
      (node (ref "D229") (pin "2") (pinfunction "K_2") (pintype "passive"))
      (node (ref "D230") (pin "2") (pinfunction "K_2") (pintype "passive"))
      (node (ref "D231") (pin "2") (pinfunction "K_2") (pintype "passive"))
      (node (ref "D232") (pin "2") (pinfunction "K_2") (pintype "passive"))
      (node (ref "D233") (pin "2") (pinfunction "K_2") (pintype "passive"))
      (node (ref "D234") (pin "2") (pinfunction "K_2") (pintype "passive"))
      (node (ref "D235") (pin "2") (pinfunction "K_2") (pintype "passive"))
      (node (ref "D236") (pin "2") (pinfunction "K_2") (pintype "passive"))
      (node (ref "D237") (pin "2") (pinfunction "K_2") (pintype "passive"))
      (node (ref "D238") (pin "2") (pinfunction "K_2") (pintype "passive"))
      (node (ref "D239") (pin "2") (pinfunction "K_2") (pintype "passive"))
      (node (ref "D240") (pin "2") (pinfunction "K_2") (pintype "passive"))
      (node (ref "D241") (pin "2") (pinfunction "K_2") (pintype "passive"))
      (node (ref "D242") (pin "2") (pinfunction "K_2") (pintype "passive"))
    )
    (net (code "19") (name "/row4") (class "Default")
      (node (ref "D243") (pin "2") (pinfunction "K_2") (pintype "passive"))
      (node (ref "D244") (pin "2") (pinfunction "K_2") (pintype "passive"))
      (node (ref "D245") (pin "2") (pinfunction "K_2") (pintype "passive"))
      (node (ref "D246") (pin "2") (pinfunction "K_2") (pintype "passive"))
      (node (ref "D247") (pin "2") (pinfunction "K_2") (pintype "passive"))
      (node (ref "D248") (pin "2") (pinfunction "K_2") (pintype "passive"))
      (node (ref "D249") (pin "2") (pinfunction "K_2") (pintype "passive"))
      (node (ref "D250") (pin "2") (pinfunction "K_2") (pintype "passive"))
      (node (ref "D251") (pin "2") (pinfunction "K_2") (pintype "passive"))
      (node (ref "D252") (pin "2") (pinfunction "K_2") (pintype "passive"))
      (node (ref "D253") (pin "2") (pinfunction "K_2") (pintype "passive"))
      (node (ref "D254") (pin "2") (pinfunction "K_2") (pintype "passive"))
      (node (ref "D255") (pin "2") (pinfunction "K_2") (pintype "passive"))
      (node (ref "D257") (pin "2") (pinfunction "K_2") (pintype "passive"))
    )
    (net (code "20") (name "/row5") (class "Default")
      (node (ref "D258") (pin "2") (pinfunction "K_2") (pintype "passive"))
      (node (ref "D259") (pin "2") (pinfunction "K_2") (pintype "passive"))
      (node (ref "D260") (pin "2") (pinfunction "K_2") (pintype "passive"))
      (node (ref "D261") (pin "2") (pinfunction "K_2") (pintype "passive"))
      (node (ref "D262") (pin "2") (pinfunction "K_2") (pintype "passive"))
      (node (ref "D263") (pin "2") (pinfunction "K_2") (pintype "passive"))
      (node (ref "D264") (pin "2") (pinfunction "K_2") (pintype "passive"))
      (node (ref "D265") (pin "2") (pinfunction "K_2") (pintype "passive"))
      (node (ref "D266") (pin "2") (pinfunction "K_2") (pintype "passive"))
      (node (ref "D267") (pin "2") (pinfunction "K_2") (pintype "passive"))
      (node (ref "D268") (pin "2") (pinfunction "K_2") (pintype "passive"))
    )
    (net (code "21") (name "Net-(D201-A)") (class "Default")
      (node (ref "D201") (pin "1") (pinfunction "A_1") (pintype "passive"))
      (node (ref "S201") (pin "1") (pinfunction "1_1") (pintype "passive"))
    )
    (net (code "22") (name "Net-(D202-A)") (class "Default")
      (node (ref "D202") (pin "1") (pinfunction "A_1") (pintype "passive"))
      (node (ref "S202") (pin "1") (pinfunction "1_1") (pintype "passive"))
    )
    (net (code "23") (name "Net-(D203-A)") (class "Default")
      (node (ref "D203") (pin "1") (pinfunction "A_1") (pintype "passive"))
      (node (ref "S203") (pin "1") (pinfunction "1_1") (pintype "passive"))
    )
    (net (code "24") (name "Net-(D204-A)") (class "Default")
      (node (ref "D204") (pin "1") (pinfunction "A_1") (pintype "passive"))
      (node (ref "S204") (pin "1") (pinfunction "1_1") (pintype "passive"))
    )
    (net (code "25") (name "Net-(D205-A)") (class "Default")
      (node (ref "D205") (pin "1") (pinfunction "A_1") (pintype "passive"))
      (node (ref "S205") (pin "1") (pinfunction "1_1") (pintype "passive"))
    )
    (net (code "26") (name "Net-(D206-A)") (class "Default")
      (node (ref "D206") (pin "1") (pinfunction "A_1") (pintype "passive"))
      (node (ref "S206") (pin "1") (pinfunction "1_1") (pintype "passive"))
    )
    (net (code "27") (name "Net-(D207-A)") (class "Default")
      (node (ref "D207") (pin "1") (pinfunction "A_1") (pintype "passive"))
      (node (ref "S207") (pin "1") (pinfunction "1_1") (pintype "passive"))
    )
    (net (code "28") (name "Net-(D208-A)") (class "Default")
      (node (ref "D208") (pin "1") (pinfunction "A_1") (pintype "passive"))
      (node (ref "S208") (pin "1") (pinfunction "1_1") (pintype "passive"))
    )
    (net (code "29") (name "Net-(D209-A)") (class "Default")
      (node (ref "D209") (pin "1") (pinfunction "A_1") (pintype "passive"))
      (node (ref "S209") (pin "1") (pinfunction "1_1") (pintype "passive"))
    )
    (net (code "30") (name "Net-(D210-A)") (class "Default")
      (node (ref "D210") (pin "1") (pinfunction "A_1") (pintype "passive"))
      (node (ref "S210") (pin "1") (pinfunction "1_1") (pintype "passive"))
    )
    (net (code "31") (name "Net-(D211-A)") (class "Default")
      (node (ref "D211") (pin "1") (pinfunction "A_1") (pintype "passive"))
      (node (ref "S211") (pin "1") (pinfunction "1_1") (pintype "passive"))
    )
    (net (code "32") (name "Net-(D212-A)") (class "Default")
      (node (ref "D212") (pin "1") (pinfunction "A_1") (pintype "passive"))
      (node (ref "S212") (pin "1") (pinfunction "1_1") (pintype "passive"))
    )
    (net (code "33") (name "Net-(D213-A)") (class "Default")
      (node (ref "D213") (pin "1") (pinfunction "A_1") (pintype "passive"))
      (node (ref "S213") (pin "1") (pinfunction "1_1") (pintype "passive"))
    )
    (net (code "34") (name "Net-(D214-A)") (class "Default")
      (node (ref "D214") (pin "1") (pinfunction "A_1") (pintype "passive"))
      (node (ref "S214") (pin "1") (pinfunction "1_1") (pintype "passive"))
    )
    (net (code "35") (name "Net-(D215-A)") (class "Default")
      (node (ref "D215") (pin "1") (pinfunction "A_1") (pintype "passive"))
      (node (ref "S215") (pin "1") (pinfunction "1_1") (pintype "passive"))
    )
    (net (code "36") (name "Net-(D216-A)") (class "Default")
      (node (ref "D216") (pin "1") (pinfunction "A_1") (pintype "passive"))
      (node (ref "S216") (pin "1") (pinfunction "1_1") (pintype "passive"))
    )
    (net (code "37") (name "Net-(D217-A)") (class "Default")
      (node (ref "D217") (pin "1") (pinfunction "A_1") (pintype "passive"))
      (node (ref "S217") (pin "1") (pinfunction "1_1") (pintype "passive"))
    )
    (net (code "38") (name "Net-(D218-A)") (class "Default")
      (node (ref "D218") (pin "1") (pinfunction "A_1") (pintype "passive"))
      (node (ref "S218") (pin "1") (pinfunction "1_1") (pintype "passive"))
    )
    (net (code "39") (name "Net-(D219-A)") (class "Default")
      (node (ref "D219") (pin "1") (pinfunction "A_1") (pintype "passive"))
      (node (ref "S219") (pin "1") (pinfunction "1_1") (pintype "passive"))
    )
    (net (code "40") (name "Net-(D220-A)") (class "Default")
      (node (ref "D220") (pin "1") (pinfunction "A_1") (pintype "passive"))
      (node (ref "S220") (pin "1") (pinfunction "1_1") (pintype "passive"))
    )
    (net (code "41") (name "Net-(D221-A)") (class "Default")
      (node (ref "D221") (pin "1") (pinfunction "A_1") (pintype "passive"))
      (node (ref "S221") (pin "1") (pinfunction "1_1") (pintype "passive"))
    )
    (net (code "42") (name "Net-(D222-A)") (class "Default")
      (node (ref "D222") (pin "1") (pinfunction "A_1") (pintype "passive"))
      (node (ref "S222") (pin "1") (pinfunction "1_1") (pintype "passive"))
    )
    (net (code "43") (name "Net-(D223-A)") (class "Default")
      (node (ref "D223") (pin "1") (pinfunction "A_1") (pintype "passive"))
      (node (ref "S223") (pin "1") (pinfunction "1_1") (pintype "passive"))
    )
    (net (code "44") (name "Net-(D224-A)") (class "Default")
      (node (ref "D224") (pin "1") (pinfunction "A_1") (pintype "passive"))
      (node (ref "S224") (pin "1") (pinfunction "1_1") (pintype "passive"))
    )
    (net (code "45") (name "Net-(D225-A)") (class "Default")
      (node (ref "D225") (pin "1") (pinfunction "A_1") (pintype "passive"))
      (node (ref "S225") (pin "1") (pinfunction "1_1") (pintype "passive"))
    )
    (net (code "46") (name "Net-(D226-A)") (class "Default")
      (node (ref "D226") (pin "1") (pinfunction "A_1") (pintype "passive"))
      (node (ref "S226") (pin "1") (pinfunction "1_1") (pintype "passive"))
    )
    (net (code "47") (name "Net-(D227-A)") (class "Default")
      (node (ref "D227") (pin "1") (pinfunction "A_1") (pintype "passive"))
      (node (ref "S227") (pin "1") (pinfunction "1_1") (pintype "passive"))
    )
    (net (code "48") (name "Net-(D228-A)") (class "Default")
      (node (ref "D228") (pin "1") (pinfunction "A_1") (pintype "passive"))
      (node (ref "S228") (pin "1") (pinfunction "1_1") (pintype "passive"))
    )
    (net (code "49") (name "Net-(D229-A)") (class "Default")
      (node (ref "D229") (pin "1") (pinfunction "A_1") (pintype "passive"))
      (node (ref "S229") (pin "2") (pinfunction "2_2") (pintype "passive"))
    )
    (net (code "50") (name "Net-(D230-A)") (class "Default")
      (node (ref "D230") (pin "1") (pinfunction "A_1") (pintype "passive"))
      (node (ref "S230") (pin "1") (pinfunction "1_1") (pintype "passive"))
    )
    (net (code "51") (name "Net-(D231-A)") (class "Default")
      (node (ref "D231") (pin "1") (pinfunction "A_1") (pintype "passive"))
      (node (ref "S231") (pin "1") (pinfunction "1_1") (pintype "passive"))
    )
    (net (code "52") (name "Net-(D232-A)") (class "Default")
      (node (ref "D232") (pin "1") (pinfunction "A_1") (pintype "passive"))
      (node (ref "S232") (pin "1") (pinfunction "1_1") (pintype "passive"))
    )
    (net (code "53") (name "Net-(D233-A)") (class "Default")
      (node (ref "D233") (pin "1") (pinfunction "A_1") (pintype "passive"))
      (node (ref "S233") (pin "1") (pinfunction "1_1") (pintype "passive"))
    )
    (net (code "54") (name "Net-(D234-A)") (class "Default")
      (node (ref "D234") (pin "1") (pinfunction "A_1") (pintype "passive"))
      (node (ref "S234") (pin "1") (pinfunction "1_1") (pintype "passive"))
    )
    (net (code "55") (name "Net-(D235-A)") (class "Default")
      (node (ref "D235") (pin "1") (pinfunction "A_1") (pintype "passive"))
      (node (ref "S235") (pin "1") (pinfunction "1_1") (pintype "passive"))
    )
    (net (code "56") (name "Net-(D236-A)") (class "Default")
      (node (ref "D236") (pin "1") (pinfunction "A_1") (pintype "passive"))
      (node (ref "S236") (pin "1") (pinfunction "1_1") (pintype "passive"))
    )
    (net (code "57") (name "Net-(D237-A)") (class "Default")
      (node (ref "D237") (pin "1") (pinfunction "A_1") (pintype "passive"))
      (node (ref "S237") (pin "1") (pinfunction "1_1") (pintype "passive"))
    )
    (net (code "58") (name "Net-(D238-A)") (class "Default")
      (node (ref "D238") (pin "1") (pinfunction "A_1") (pintype "passive"))
      (node (ref "S238") (pin "1") (pinfunction "1_1") (pintype "passive"))
    )
    (net (code "59") (name "Net-(D239-A)") (class "Default")
      (node (ref "D239") (pin "1") (pinfunction "A_1") (pintype "passive"))
      (node (ref "S239") (pin "1") (pinfunction "1_1") (pintype "passive"))
    )
    (net (code "60") (name "Net-(D240-A)") (class "Default")
      (node (ref "D240") (pin "1") (pinfunction "A_1") (pintype "passive"))
      (node (ref "S240") (pin "1") (pinfunction "1_1") (pintype "passive"))
    )
    (net (code "61") (name "Net-(D241-A)") (class "Default")
      (node (ref "D241") (pin "1") (pinfunction "A_1") (pintype "passive"))
      (node (ref "S241") (pin "1") (pinfunction "1_1") (pintype "passive"))
    )
    (net (code "62") (name "Net-(D243-A)") (class "Default")
      (node (ref "D243") (pin "1") (pinfunction "A_1") (pintype "passive"))
      (node (ref "S243") (pin "1") (pinfunction "1_1") (pintype "passive"))
    )
    (net (code "63") (name "Net-(D244-A)") (class "Default")
      (node (ref "D244") (pin "1") (pinfunction "A_1") (pintype "passive"))
      (node (ref "S244") (pin "2") (pinfunction "2_2") (pintype "passive"))
    )
    (net (code "64") (name "Net-(D245-A)") (class "Default")
      (node (ref "D245") (pin "1") (pinfunction "A_1") (pintype "passive"))
      (node (ref "S245") (pin "1") (pinfunction "1_1") (pintype "passive"))
    )
    (net (code "65") (name "Net-(D246-A)") (class "Default")
      (node (ref "D246") (pin "1") (pinfunction "A_1") (pintype "passive"))
      (node (ref "S246") (pin "1") (pinfunction "1_1") (pintype "passive"))
    )
    (net (code "66") (name "Net-(D247-A)") (class "Default")
      (node (ref "D247") (pin "1") (pinfunction "A_1") (pintype "passive"))
      (node (ref "S247") (pin "1") (pinfunction "1_1") (pintype "passive"))
    )
    (net (code "67") (name "Net-(D248-A)") (class "Default")
      (node (ref "D248") (pin "1") (pinfunction "A_1") (pintype "passive"))
      (node (ref "S248") (pin "1") (pinfunction "1_1") (pintype "passive"))
    )
    (net (code "68") (name "Net-(D249-A)") (class "Default")
      (node (ref "D249") (pin "1") (pinfunction "A_1") (pintype "passive"))
      (node (ref "S249") (pin "1") (pinfunction "1_1") (pintype "passive"))
    )
    (net (code "69") (name "Net-(D250-A)") (class "Default")
      (node (ref "D250") (pin "1") (pinfunction "A_1") (pintype "passive"))
      (node (ref "S250") (pin "1") (pinfunction "1_1") (pintype "passive"))
    )
    (net (code "70") (name "Net-(D251-A)") (class "Default")
      (node (ref "D251") (pin "1") (pinfunction "A_1") (pintype "passive"))
      (node (ref "S251") (pin "1") (pinfunction "1_1") (pintype "passive"))
    )
    (net (code "71") (name "Net-(D252-A)") (class "Default")
      (node (ref "D252") (pin "1") (pinfunction "A_1") (pintype "passive"))
      (node (ref "S252") (pin "1") (pinfunction "1_1") (pintype "passive"))
    )
    (net (code "72") (name "Net-(D253-A)") (class "Default")
      (node (ref "D253") (pin "1") (pinfunction "A_1") (pintype "passive"))
      (node (ref "S253") (pin "1") (pinfunction "1_1") (pintype "passive"))
    )
    (net (code "73") (name "Net-(D254-A)") (class "Default")
      (node (ref "D254") (pin "1") (pinfunction "A_1") (pintype "passive"))
      (node (ref "S254") (pin "1") (pinfunction "1_1") (pintype "passive"))
    )
    (net (code "74") (name "Net-(D255-A)") (class "Default")
      (node (ref "D255") (pin "1") (pinfunction "A_1") (pintype "passive"))
      (node (ref "S256") (pin "1") (pinfunction "1_1") (pintype "passive"))
    )
    (net (code "75") (name "Net-(D257-A)") (class "Default")
      (node (ref "D257") (pin "1") (pinfunction "A_1") (pintype "passive"))
      (node (ref "S257") (pin "1") (pinfunction "1_1") (pintype "passive"))
      (node (ref "S257_1") (pin "1") (pinfunction "1_1") (pintype "passive"))
    )
    (net (code "76") (name "Net-(D258-A)") (class "Default")
      (node (ref "D258") (pin "1") (pinfunction "A_1") (pintype "passive"))
      (node (ref "S258") (pin "2") (pinfunction "2_2") (pintype "passive"))
    )
    (net (code "77") (name "Net-(D259-A)") (class "Default")
      (node (ref "D259") (pin "1") (pinfunction "A_1") (pintype "passive"))
      (node (ref "S259") (pin "1") (pinfunction "1_1") (pintype "passive"))
    )
    (net (code "78") (name "Net-(D260-A)") (class "Default")
      (node (ref "D260") (pin "1") (pinfunction "A_1") (pintype "passive"))
      (node (ref "S260") (pin "1") (pinfunction "1_1") (pintype "passive"))
    )
    (net (code "79") (name "Net-(D261-A)") (class "Default")
      (node (ref "D261") (pin "1") (pinfunction "A_1") (pintype "passive"))
      (node (ref "S261") (pin "1") (pinfunction "1_1") (pintype "passive"))
      (node (ref "S261_1") (pin "1") (pinfunction "1_1") (pintype "passive"))
    )
    (net (code "80") (name "Net-(D262-A)") (class "Default")
      (node (ref "D262") (pin "1") (pinfunction "A_1") (pintype "passive"))
      (node (ref "S262") (pin "2") (pinfunction "2_2") (pintype "passive"))
      (node (ref "S262_1") (pin "1") (pinfunction "1_1") (pintype "passive"))
    )
    (net (code "81") (name "Net-(D263-A)") (class "Default")
      (node (ref "D263") (pin "1") (pinfunction "A_1") (pintype "passive"))
      (node (ref "S263") (pin "2") (pinfunction "2_2") (pintype "passive"))
      (node (ref "S263_1") (pin "2") (pinfunction "2_2") (pintype "passive"))
    )
    (net (code "82") (name "Net-(D264-A)") (class "Default")
      (node (ref "D264") (pin "1") (pinfunction "A_1") (pintype "passive"))
      (node (ref "S264") (pin "1") (pinfunction "1_1") (pintype "passive"))
      (node (ref "S264_2") (pin "1") (pinfunction "1_1") (pintype "passive"))
    )
    (net (code "83") (name "Net-(D265-A)") (class "Default")
      (node (ref "D265") (pin "1") (pinfunction "A_1") (pintype "passive"))
      (node (ref "S265") (pin "2") (pinfunction "2_2") (pintype "passive"))
      (node (ref "S265_2") (pin "1") (pinfunction "1_1") (pintype "passive"))
    )
    (net (code "84") (name "Net-(D266-A)") (class "Default")
      (node (ref "D266") (pin "1") (pinfunction "A_1") (pintype "passive"))
      (node (ref "S266") (pin "2") (pinfunction "2_2") (pintype "passive"))
    )
    (net (code "85") (name "Net-(D267-A)") (class "Default")
      (node (ref "D267") (pin "1") (pinfunction "A_1") (pintype "passive"))
      (node (ref "S267") (pin "1") (pinfunction "1_1") (pintype "passive"))
    )
    (net (code "86") (name "Net-(D268-A)") (class "Default")
      (node (ref "D268") (pin "1") (pinfunction "A_1") (pintype "passive"))
      (node (ref "S268") (pin "1") (pinfunction "1_1") (pintype "passive"))
    )
    (net (code "87") (name "unconnected-(STAB1-Pad1)") (class "Default")
      (node (ref "STAB1") (pin "1") (pinfunction "1_1") (pintype "passive"))
    )
    (net (code "88") (name "unconnected-(STAB2-Pad1)") (class "Default")
      (node (ref "STAB2") (pin "1") (pinfunction "1_1") (pintype "passive"))
    )
    (net (code "89") (name "unconnected-(STAB3-Pad1)") (class "Default")
      (node (ref "STAB3") (pin "1") (pinfunction "1_1") (pintype "passive"))
    )
  )
)
